# C-06_CPU_IO_PHY.net
KiCad netlist of a schematic drawn in Altium Designer
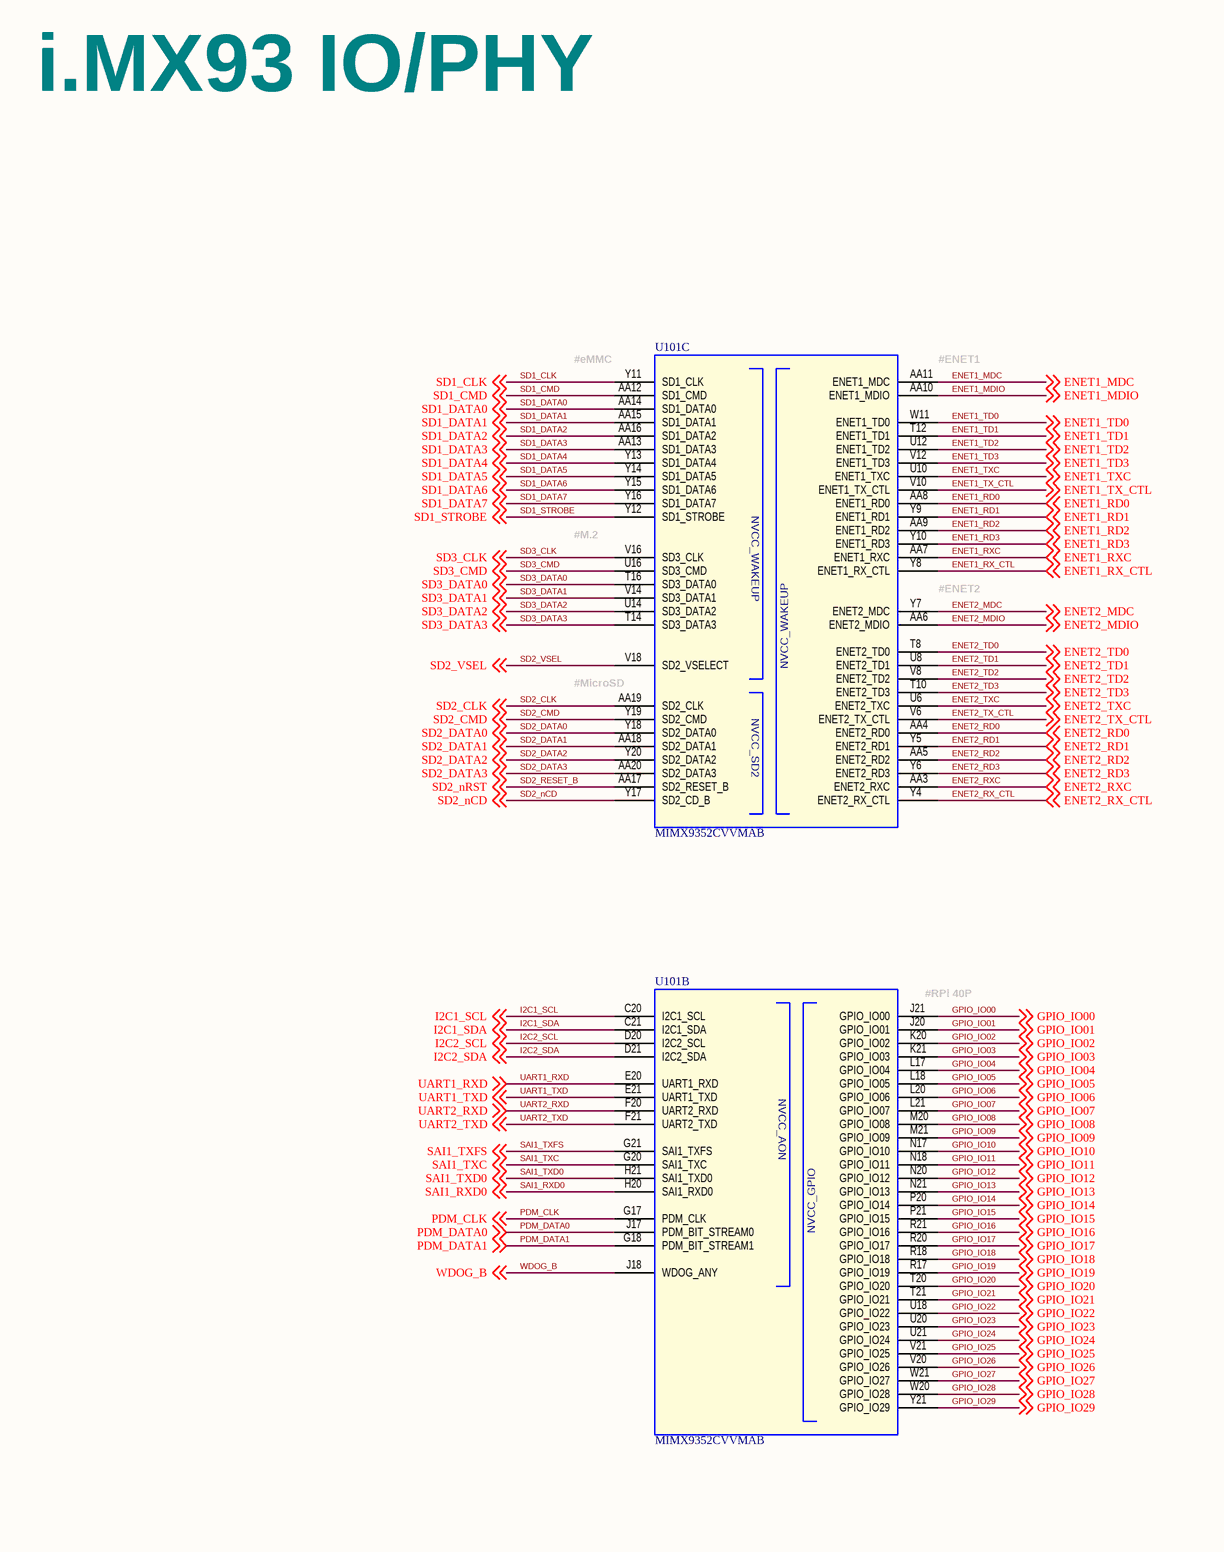
[diagram p0: C-06 CPU IO_PHY.SchDoc, left]
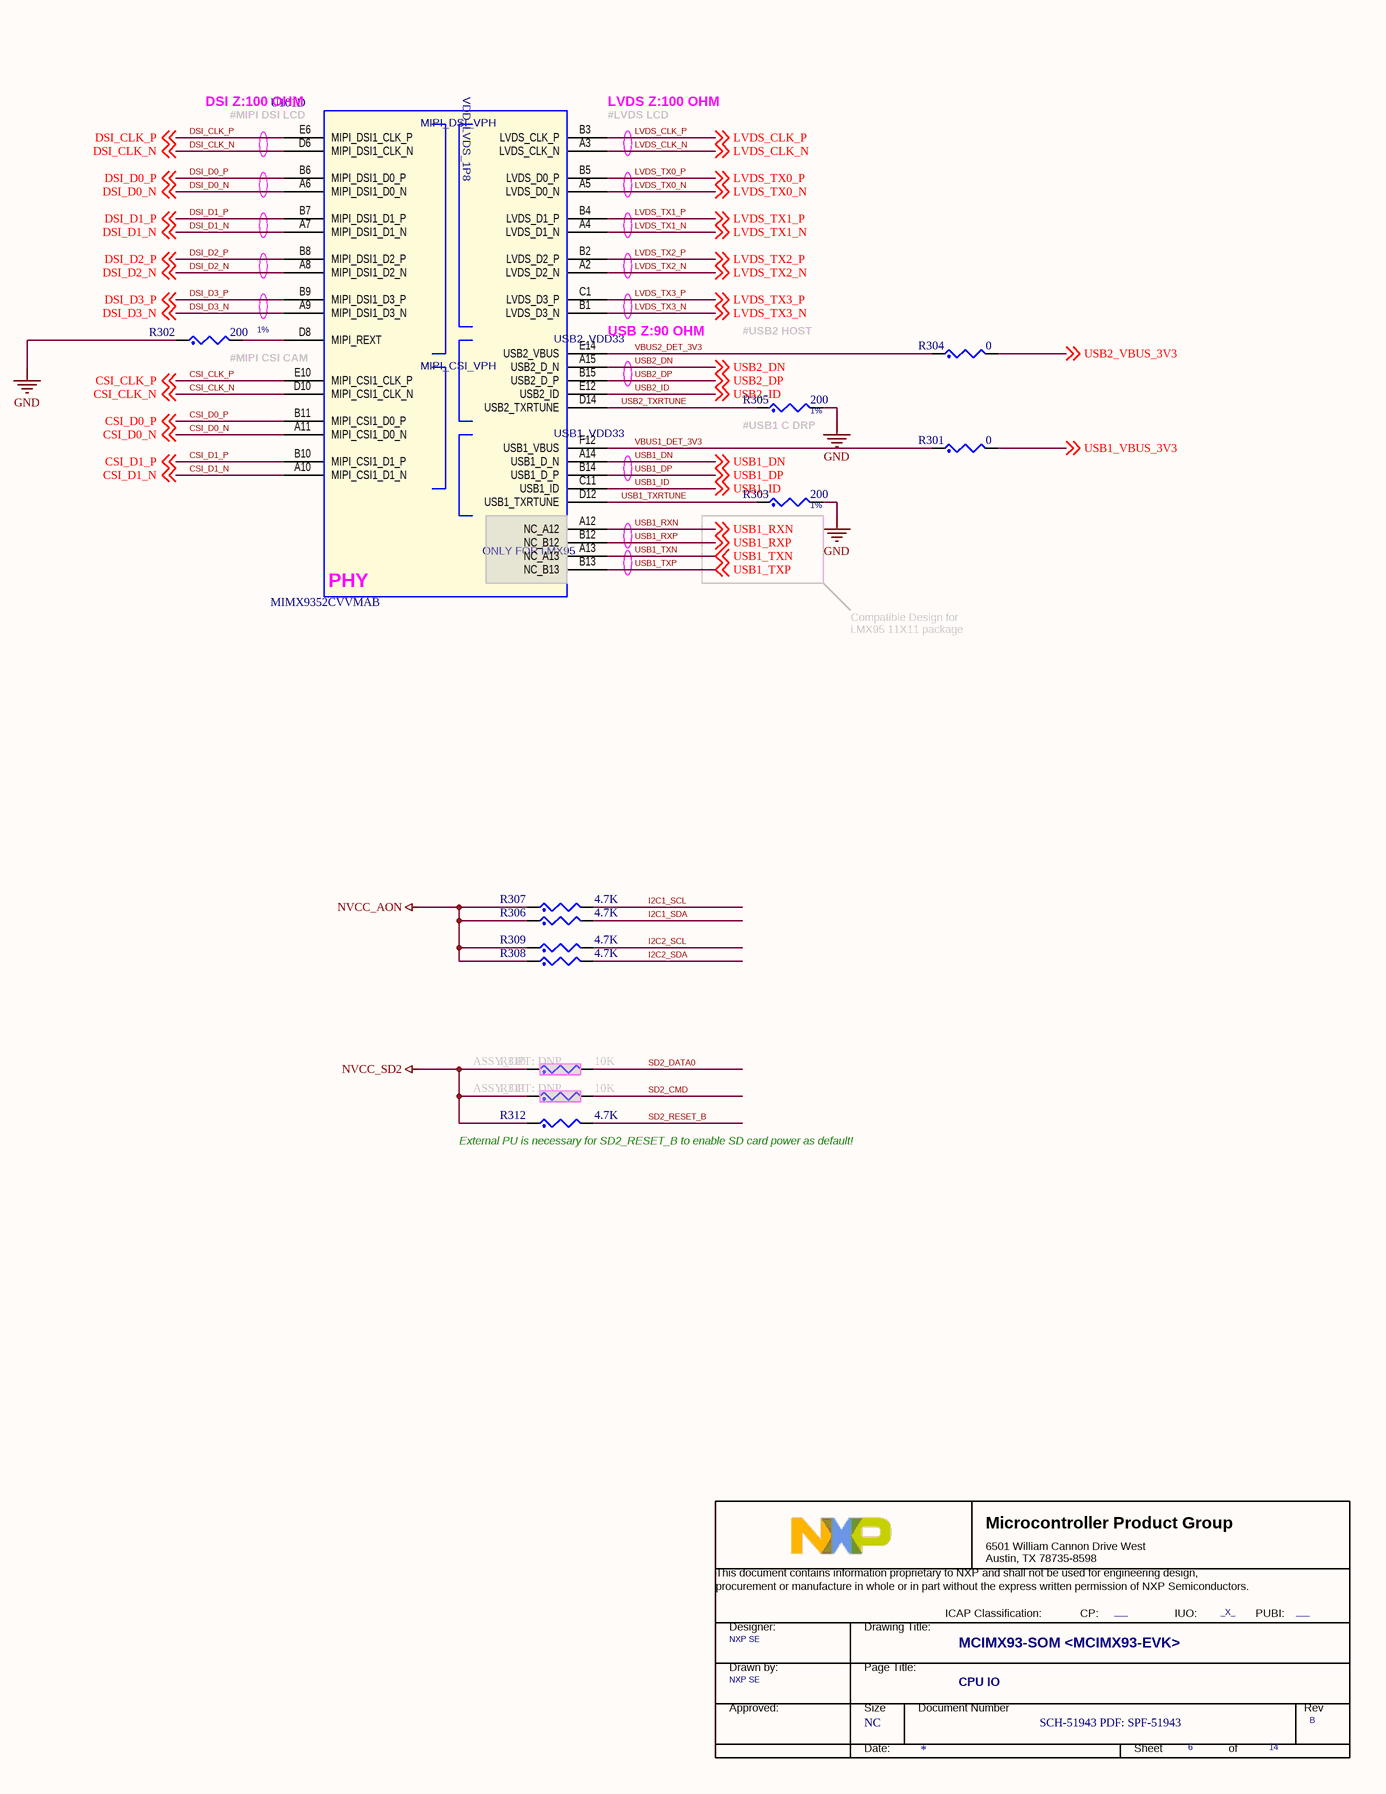
[diagram p1: C-06 CPU IO_PHY.SchDoc, right]

(export (version "E")
  (design (tool "Eeschema 10.0.6"))
  (components
    (comp (ref "R301")
      (value "0")
      (footprint "0201_CC")
      (description "RES MF ZERO OHM 1/20W -- 0201")
      (libsource (lib "*") (part "RES"))
    )
    (comp (ref "R302")
      (value "200")
      (footprint "0201_CC")
      (description "RES MF 200 OHM 1/20W 1% 0201")
      (fields (field (name "VOLTAGE") "25V") (field (name "TOLERANCE") "1%"))
      (libsource (lib "*") (part "RES"))
    )
    (comp (ref "R303")
      (value "200")
      (footprint "0201_CC")
      (description "RES MF 200 OHM 1/20W 1% 0201")
      (fields (field (name "TOLERANCE") "1%") (field (name "VOLTAGE") "25V"))
      (libsource (lib "*") (part "RES"))
    )
    (comp (ref "R304")
      (value "0")
      (footprint "0201_CC")
      (description "RES MF ZERO OHM 1/20W -- 0201")
      (libsource (lib "*") (part "RES"))
    )
    (comp (ref "R305")
      (value "200")
      (footprint "0201_CC")
      (description "RES MF 200 OHM 1/20W 1% 0201")
      (fields (field (name "TOLERANCE") "1%") (field (name "VOLTAGE") "25V"))
      (libsource (lib "*") (part "RES"))
    )
    (comp (ref "R306")
      (value "4.7K")
      (footprint "0402_CC")
      (description "RES MF 4.7K 1/10W 5% AEC-Q200 0402")
      (fields (field (name "VOLTAGE") "50V") (field (name "TOLERANCE") "5%"))
      (libsource (lib "*") (part "RES"))
    )
    (comp (ref "R307")
      (value "4.7K")
      (footprint "0402_CC")
      (description "RES MF 4.7K 1/10W 5% AEC-Q200 0402")
      (fields (field (name "TOLERANCE") "5%") (field (name "VOLTAGE") "50V"))
      (libsource (lib "*") (part "RES"))
    )
    (comp (ref "R308")
      (value "4.7K")
      (footprint "0402_CC")
      (description "RES MF 4.7K 1/10W 5% AEC-Q200 0402")
      (fields (field (name "TOLERANCE") "5%") (field (name "VOLTAGE") "50V"))
      (libsource (lib "*") (part "RES"))
    )
    (comp (ref "R309")
      (value "4.7K")
      (footprint "0402_CC")
      (description "RES MF 4.7K 1/10W 5% AEC-Q200 0402")
      (fields (field (name "TOLERANCE") "5%") (field (name "VOLTAGE") "50V"))
      (libsource (lib "*") (part "RES"))
    )
    (comp (ref "R310")
      (value "10K")
      (footprint "0402_CC")
      (description "RES MF 10K 1/16W 5% 0402")
      (fields (field (name "ASSY_OPT") "DNP") (field (name "TOLERANCE") "5%"))
      (libsource (lib "*") (part "RES"))
    )
    (comp (ref "R311")
      (value "10K")
      (footprint "0402_CC")
      (description "RES MF 10K 1/16W 5% 0402")
      (fields (field (name "ASSY_OPT") "DNP") (field (name "TOLERANCE") "5%"))
      (libsource (lib "*") (part "RES"))
    )
    (comp (ref "R312")
      (value "4.7K")
      (footprint "0402_CC")
      (description "RES MF 4.7K 1/10W 5% AEC-Q200 0402")
      (fields (field (name "TOLERANCE") "5%") (field (name "VOLTAGE") "50V"))
      (libsource (lib "*") (part "RES"))
    )
    (comp (ref "U101")
      (value "MIMX9352CVVMAB")
      (footprint "SKT_BGA306_0P5_SQ16P23_ELAST")
      (description "SUBASSEMBLY SKT 306 BGA ELASTOMER SMT 0.5MM 395H AU + IC CPU 1.7GHz -- FCBGA306")
      (libsource (lib "*") (part "MIMX9352DVNxLAA"))
    )
  )
  (nets
    (net (code "1") (name "/USB1_TXRTUNE") (class "Default")
      (node (ref "R303") (pin "1") (pinfunction "1_1") (pintype "passive"))
      (node (ref "U101") (pin "D12") (pinfunction "USB1_TXRTUNE_D12") (pintype "passive"))
    )
    (net (code "2") (name "/USB2_TXRTUNE") (class "Default")
      (node (ref "R305") (pin "1") (pinfunction "1_1") (pintype "passive"))
      (node (ref "U101") (pin "D14") (pinfunction "USB2_TXRTUNE_D14") (pintype "passive"))
    )
    (net (code "3") (name "/VBUS1_DET_3V3") (class "Default")
      (node (ref "R301") (pin "1") (pinfunction "1_1") (pintype "passive"))
      (node (ref "U101") (pin "F12") (pinfunction "USB1_VBUS_F12") (pintype "passive"))
    )
    (net (code "4") (name "/VBUS2_DET_3V3") (class "Default")
      (node (ref "R304") (pin "1") (pinfunction "1_1") (pintype "passive"))
      (node (ref "U101") (pin "E14") (pinfunction "USB2_VBUS_E14") (pintype "passive"))
    )
    (net (code "5") (name "CSI_CLK_N") (class "Default")
      (node (ref "U101") (pin "D10") (pinfunction "MIPI_CSI1_CLK_N_D10") (pintype "passive"))
    )
    (net (code "6") (name "CSI_CLK_P") (class "Default")
      (node (ref "U101") (pin "E10") (pinfunction "MIPI_CSI1_CLK_P_E10") (pintype "passive"))
    )
    (net (code "7") (name "CSI_D0_N") (class "Default")
      (node (ref "U101") (pin "A11") (pinfunction "MIPI_CSI1_D0_N_A11") (pintype "passive"))
    )
    (net (code "8") (name "CSI_D0_P") (class "Default")
      (node (ref "U101") (pin "B11") (pinfunction "MIPI_CSI1_D0_P_B11") (pintype "passive"))
    )
    (net (code "9") (name "CSI_D1_N") (class "Default")
      (node (ref "U101") (pin "A10") (pinfunction "MIPI_CSI1_D1_N_A10") (pintype "passive"))
    )
    (net (code "10") (name "CSI_D1_P") (class "Default")
      (node (ref "U101") (pin "B10") (pinfunction "MIPI_CSI1_D1_P_B10") (pintype "passive"))
    )
    (net (code "11") (name "DSI_CLK_N") (class "Default")
      (node (ref "U101") (pin "D6") (pinfunction "MIPI_DSI1_CLK_N_D6") (pintype "passive"))
    )
    (net (code "12") (name "DSI_CLK_P") (class "Default")
      (node (ref "U101") (pin "E6") (pinfunction "MIPI_DSI1_CLK_P_E6") (pintype "passive"))
    )
    (net (code "13") (name "DSI_D0_N") (class "Default")
      (node (ref "U101") (pin "A6") (pinfunction "MIPI_DSI1_D0_N_A6") (pintype "passive"))
    )
    (net (code "14") (name "DSI_D0_P") (class "Default")
      (node (ref "U101") (pin "B6") (pinfunction "MIPI_DSI1_D0_P_B6") (pintype "passive"))
    )
    (net (code "15") (name "DSI_D1_N") (class "Default")
      (node (ref "U101") (pin "A7") (pinfunction "MIPI_DSI1_D1_N_A7") (pintype "passive"))
    )
    (net (code "16") (name "DSI_D1_P") (class "Default")
      (node (ref "U101") (pin "B7") (pinfunction "MIPI_DSI1_D1_P_B7") (pintype "passive"))
    )
    (net (code "17") (name "DSI_D2_N") (class "Default")
      (node (ref "U101") (pin "A8") (pinfunction "MIPI_DSI1_D2_N_A8") (pintype "passive"))
    )
    (net (code "18") (name "DSI_D2_P") (class "Default")
      (node (ref "U101") (pin "B8") (pinfunction "MIPI_DSI1_D2_P_B8") (pintype "passive"))
    )
    (net (code "19") (name "DSI_D3_N") (class "Default")
      (node (ref "U101") (pin "A9") (pinfunction "MIPI_DSI1_D3_N_A9") (pintype "passive"))
    )
    (net (code "20") (name "DSI_D3_P") (class "Default")
      (node (ref "U101") (pin "B9") (pinfunction "MIPI_DSI1_D3_P_B9") (pintype "passive"))
    )
    (net (code "21") (name "ENET1_MDC") (class "Default")
      (node (ref "U101") (pin "AA11") (pinfunction "ENET1_MDC_AA11") (pintype "passive"))
    )
    (net (code "22") (name "ENET1_MDIO") (class "Default")
      (node (ref "U101") (pin "AA10") (pinfunction "ENET1_MDIO_AA10") (pintype "passive"))
    )
    (net (code "23") (name "ENET1_RD0") (class "Default")
      (node (ref "U101") (pin "AA8") (pinfunction "ENET1_RD0_AA8") (pintype "passive"))
    )
    (net (code "24") (name "ENET1_RD1") (class "Default")
      (node (ref "U101") (pin "Y9") (pinfunction "ENET1_RD1_Y9") (pintype "passive"))
    )
    (net (code "25") (name "ENET1_RD2") (class "Default")
      (node (ref "U101") (pin "AA9") (pinfunction "ENET1_RD2_AA9") (pintype "passive"))
    )
    (net (code "26") (name "ENET1_RD3") (class "Default")
      (node (ref "U101") (pin "Y10") (pinfunction "ENET1_RD3_Y10") (pintype "passive"))
    )
    (net (code "27") (name "ENET1_RXC") (class "Default")
      (node (ref "U101") (pin "AA7") (pinfunction "ENET1_RXC_AA7") (pintype "passive"))
    )
    (net (code "28") (name "ENET1_RX_CTL") (class "Default")
      (node (ref "U101") (pin "Y8") (pinfunction "ENET1_RX_CTL_Y8") (pintype "passive"))
    )
    (net (code "29") (name "ENET1_TD0") (class "Default")
      (node (ref "U101") (pin "W11") (pinfunction "ENET1_TD0_W11") (pintype "passive"))
    )
    (net (code "30") (name "ENET1_TD1") (class "Default")
      (node (ref "U101") (pin "T12") (pinfunction "ENET1_TD1_T12") (pintype "passive"))
    )
    (net (code "31") (name "ENET1_TD2") (class "Default")
      (node (ref "U101") (pin "U12") (pinfunction "ENET1_TD2_U12") (pintype "passive"))
    )
    (net (code "32") (name "ENET1_TD3") (class "Default")
      (node (ref "U101") (pin "V12") (pinfunction "ENET1_TD3_V12") (pintype "passive"))
    )
    (net (code "33") (name "ENET1_TXC") (class "Default")
      (node (ref "U101") (pin "U10") (pinfunction "ENET1_TXC_U10") (pintype "passive"))
    )
    (net (code "34") (name "ENET1_TX_CTL") (class "Default")
      (node (ref "U101") (pin "V10") (pinfunction "ENET1_TX_CTL_V10") (pintype "passive"))
    )
    (net (code "35") (name "ENET2_MDC") (class "Default")
      (node (ref "U101") (pin "Y7") (pinfunction "ENET2_MDC_Y7") (pintype "passive"))
    )
    (net (code "36") (name "ENET2_MDIO") (class "Default")
      (node (ref "U101") (pin "AA6") (pinfunction "ENET2_MDIO_AA6") (pintype "passive"))
    )
    (net (code "37") (name "ENET2_RD0") (class "Default")
      (node (ref "U101") (pin "AA4") (pinfunction "ENET2_RD0_AA4") (pintype "passive"))
    )
    (net (code "38") (name "ENET2_RD1") (class "Default")
      (node (ref "U101") (pin "Y5") (pinfunction "ENET2_RD1_Y5") (pintype "passive"))
    )
    (net (code "39") (name "ENET2_RD2") (class "Default")
      (node (ref "U101") (pin "AA5") (pinfunction "ENET2_RD2_AA5") (pintype "passive"))
    )
    (net (code "40") (name "ENET2_RD3") (class "Default")
      (node (ref "U101") (pin "Y6") (pinfunction "ENET2_RD3_Y6") (pintype "passive"))
    )
    (net (code "41") (name "ENET2_RXC") (class "Default")
      (node (ref "U101") (pin "AA3") (pinfunction "ENET2_RXC_AA3") (pintype "passive"))
    )
    (net (code "42") (name "ENET2_RX_CTL") (class "Default")
      (node (ref "U101") (pin "Y4") (pinfunction "ENET2_RX_CTL_Y4") (pintype "passive"))
    )
    (net (code "43") (name "ENET2_TD0") (class "Default")
      (node (ref "U101") (pin "T8") (pinfunction "ENET2_TD0_T8") (pintype "passive"))
    )
    (net (code "44") (name "ENET2_TD1") (class "Default")
      (node (ref "U101") (pin "U8") (pinfunction "ENET2_TD1_U8") (pintype "passive"))
    )
    (net (code "45") (name "ENET2_TD2") (class "Default")
      (node (ref "U101") (pin "V8") (pinfunction "ENET2_TD2_V8") (pintype "passive"))
    )
    (net (code "46") (name "ENET2_TD3") (class "Default")
      (node (ref "U101") (pin "T10") (pinfunction "ENET2_TD3_T10") (pintype "passive"))
    )
    (net (code "47") (name "ENET2_TXC") (class "Default")
      (node (ref "U101") (pin "U6") (pinfunction "ENET2_TXC_U6") (pintype "passive"))
    )
    (net (code "48") (name "ENET2_TX_CTL") (class "Default")
      (node (ref "U101") (pin "V6") (pinfunction "ENET2_TX_CTL_V6") (pintype "passive"))
    )
    (net (code "49") (name "GND") (class "Default")
      (node (ref "R302") (pin "1") (pinfunction "1_1") (pintype "passive"))
      (node (ref "R303") (pin "2") (pinfunction "2_2") (pintype "passive"))
      (node (ref "R305") (pin "2") (pinfunction "2_2") (pintype "passive"))
    )
    (net (code "50") (name "GPIO_IO00") (class "Default")
      (node (ref "U101") (pin "J21") (pinfunction "GPIO_IO00_J21") (pintype "passive"))
    )
    (net (code "51") (name "GPIO_IO01") (class "Default")
      (node (ref "U101") (pin "J20") (pinfunction "GPIO_IO01_J20") (pintype "passive"))
    )
    (net (code "52") (name "GPIO_IO02") (class "Default")
      (node (ref "U101") (pin "K20") (pinfunction "GPIO_IO02_K20") (pintype "passive"))
    )
    (net (code "53") (name "GPIO_IO03") (class "Default")
      (node (ref "U101") (pin "K21") (pinfunction "GPIO_IO03_K21") (pintype "passive"))
    )
    (net (code "54") (name "GPIO_IO04") (class "Default")
      (node (ref "U101") (pin "L17") (pinfunction "GPIO_IO04_L17") (pintype "passive"))
    )
    (net (code "55") (name "GPIO_IO05") (class "Default")
      (node (ref "U101") (pin "L18") (pinfunction "GPIO_IO05_L18") (pintype "passive"))
    )
    (net (code "56") (name "GPIO_IO06") (class "Default")
      (node (ref "U101") (pin "L20") (pinfunction "GPIO_IO06_L20") (pintype "passive"))
    )
    (net (code "57") (name "GPIO_IO07") (class "Default")
      (node (ref "U101") (pin "L21") (pinfunction "GPIO_IO07_L21") (pintype "passive"))
    )
    (net (code "58") (name "GPIO_IO08") (class "Default")
      (node (ref "U101") (pin "M20") (pinfunction "GPIO_IO08_M20") (pintype "passive"))
    )
    (net (code "59") (name "GPIO_IO09") (class "Default")
      (node (ref "U101") (pin "M21") (pinfunction "GPIO_IO09_M21") (pintype "passive"))
    )
    (net (code "60") (name "GPIO_IO10") (class "Default")
      (node (ref "U101") (pin "N17") (pinfunction "GPIO_IO10_N17") (pintype "passive"))
    )
    (net (code "61") (name "GPIO_IO11") (class "Default")
      (node (ref "U101") (pin "N18") (pinfunction "GPIO_IO11_N18") (pintype "passive"))
    )
    (net (code "62") (name "GPIO_IO12") (class "Default")
      (node (ref "U101") (pin "N20") (pinfunction "GPIO_IO12_N20") (pintype "passive"))
    )
    (net (code "63") (name "GPIO_IO13") (class "Default")
      (node (ref "U101") (pin "N21") (pinfunction "GPIO_IO13_N21") (pintype "passive"))
    )
    (net (code "64") (name "GPIO_IO14") (class "Default")
      (node (ref "U101") (pin "P20") (pinfunction "GPIO_IO14_P20") (pintype "passive"))
    )
    (net (code "65") (name "GPIO_IO15") (class "Default")
      (node (ref "U101") (pin "P21") (pinfunction "GPIO_IO15_P21") (pintype "passive"))
    )
    (net (code "66") (name "GPIO_IO16") (class "Default")
      (node (ref "U101") (pin "R21") (pinfunction "GPIO_IO16_R21") (pintype "passive"))
    )
    (net (code "67") (name "GPIO_IO17") (class "Default")
      (node (ref "U101") (pin "R20") (pinfunction "GPIO_IO17_R20") (pintype "passive"))
    )
    (net (code "68") (name "GPIO_IO18") (class "Default")
      (node (ref "U101") (pin "R18") (pinfunction "GPIO_IO18_R18") (pintype "passive"))
    )
    (net (code "69") (name "GPIO_IO19") (class "Default")
      (node (ref "U101") (pin "R17") (pinfunction "GPIO_IO19_R17") (pintype "passive"))
    )
    (net (code "70") (name "GPIO_IO20") (class "Default")
      (node (ref "U101") (pin "T20") (pinfunction "GPIO_IO20_T20") (pintype "passive"))
    )
    (net (code "71") (name "GPIO_IO21") (class "Default")
      (node (ref "U101") (pin "T21") (pinfunction "GPIO_IO21_T21") (pintype "passive"))
    )
    (net (code "72") (name "GPIO_IO22") (class "Default")
      (node (ref "U101") (pin "U18") (pinfunction "GPIO_IO22_U18") (pintype "passive"))
    )
    (net (code "73") (name "GPIO_IO23") (class "Default")
      (node (ref "U101") (pin "U20") (pinfunction "GPIO_IO23_U20") (pintype "passive"))
    )
    (net (code "74") (name "GPIO_IO24") (class "Default")
      (node (ref "U101") (pin "U21") (pinfunction "GPIO_IO24_U21") (pintype "passive"))
    )
    (net (code "75") (name "GPIO_IO25") (class "Default")
      (node (ref "U101") (pin "V21") (pinfunction "GPIO_IO25_V21") (pintype "passive"))
    )
    (net (code "76") (name "GPIO_IO26") (class "Default")
      (node (ref "U101") (pin "V20") (pinfunction "GPIO_IO26_V20") (pintype "passive"))
    )
    (net (code "77") (name "GPIO_IO27") (class "Default")
      (node (ref "U101") (pin "W21") (pinfunction "GPIO_IO27_W21") (pintype "passive"))
    )
    (net (code "78") (name "GPIO_IO28") (class "Default")
      (node (ref "U101") (pin "W20") (pinfunction "GPIO_IO28_W20") (pintype "passive"))
    )
    (net (code "79") (name "GPIO_IO29") (class "Default")
      (node (ref "U101") (pin "Y21") (pinfunction "GPIO_IO29_Y21") (pintype "passive"))
    )
    (net (code "80") (name "I2C1_SCL") (class "Default")
      (node (ref "R307") (pin "2") (pinfunction "2_2") (pintype "passive"))
      (node (ref "U101") (pin "C20") (pinfunction "I2C1_SCL_C20") (pintype "passive"))
    )
    (net (code "81") (name "I2C1_SDA") (class "Default")
      (node (ref "R306") (pin "2") (pinfunction "2_2") (pintype "passive"))
      (node (ref "U101") (pin "C21") (pinfunction "I2C1_SDA_C21") (pintype "passive"))
    )
    (net (code "82") (name "I2C2_SCL") (class "Default")
      (node (ref "R309") (pin "2") (pinfunction "2_2") (pintype "passive"))
      (node (ref "U101") (pin "D20") (pinfunction "I2C2_SCL_D20") (pintype "passive"))
    )
    (net (code "83") (name "I2C2_SDA") (class "Default")
      (node (ref "R308") (pin "2") (pinfunction "2_2") (pintype "passive"))
      (node (ref "U101") (pin "D21") (pinfunction "I2C2_SDA_D21") (pintype "passive"))
    )
    (net (code "84") (name "LVDS_CLK_N") (class "Default")
      (node (ref "U101") (pin "A3") (pinfunction "LVDS_CLK_N_A3") (pintype "passive"))
    )
    (net (code "85") (name "LVDS_CLK_P") (class "Default")
      (node (ref "U101") (pin "B3") (pinfunction "LVDS_CLK_P_B3") (pintype "passive"))
    )
    (net (code "86") (name "LVDS_TX0_N") (class "Default")
      (node (ref "U101") (pin "A5") (pinfunction "LVDS_D0_N_A5") (pintype "passive"))
    )
    (net (code "87") (name "LVDS_TX0_P") (class "Default")
      (node (ref "U101") (pin "B5") (pinfunction "LVDS_D0_P_B5") (pintype "passive"))
    )
    (net (code "88") (name "LVDS_TX1_N") (class "Default")
      (node (ref "U101") (pin "A4") (pinfunction "LVDS_D1_N_A4") (pintype "passive"))
    )
    (net (code "89") (name "LVDS_TX1_P") (class "Default")
      (node (ref "U101") (pin "B4") (pinfunction "LVDS_D1_P_B4") (pintype "passive"))
    )
    (net (code "90") (name "LVDS_TX2_N") (class "Default")
      (node (ref "U101") (pin "A2") (pinfunction "LVDS_D2_N_A2") (pintype "passive"))
    )
    (net (code "91") (name "LVDS_TX2_P") (class "Default")
      (node (ref "U101") (pin "B2") (pinfunction "LVDS_D2_P_B2") (pintype "passive"))
    )
    (net (code "92") (name "LVDS_TX3_N") (class "Default")
      (node (ref "U101") (pin "B1") (pinfunction "LVDS_D3_N_B1") (pintype "passive"))
    )
    (net (code "93") (name "LVDS_TX3_P") (class "Default")
      (node (ref "U101") (pin "C1") (pinfunction "LVDS_D3_P_C1") (pintype "passive"))
    )
    (net (code "94") (name "NVCC_AON") (class "Default")
      (node (ref "R306") (pin "1") (pinfunction "1_1") (pintype "passive"))
      (node (ref "R307") (pin "1") (pinfunction "1_1") (pintype "passive"))
      (node (ref "R308") (pin "1") (pinfunction "1_1") (pintype "passive"))
      (node (ref "R309") (pin "1") (pinfunction "1_1") (pintype "passive"))
    )
    (net (code "95") (name "NVCC_SD2") (class "Default")
      (node (ref "R310") (pin "1") (pinfunction "1_1") (pintype "passive"))
      (node (ref "R311") (pin "1") (pinfunction "1_1") (pintype "passive"))
      (node (ref "R312") (pin "1") (pinfunction "1_1") (pintype "passive"))
    )
    (net (code "96") (name "Net-(U101D-MIPI_REXT)") (class "Default")
      (node (ref "R302") (pin "2") (pinfunction "2_2") (pintype "passive"))
      (node (ref "U101") (pin "D8") (pinfunction "MIPI_REXT_D8") (pintype "passive"))
    )
    (net (code "97") (name "PDM_CLK") (class "Default")
      (node (ref "U101") (pin "G17") (pinfunction "PDM_CLK_G17") (pintype "passive"))
    )
    (net (code "98") (name "PDM_DATA0") (class "Default")
      (node (ref "U101") (pin "J17") (pinfunction "PDM_BIT_STREAM0_J17") (pintype "passive"))
    )
    (net (code "99") (name "PDM_DATA1") (class "Default")
      (node (ref "U101") (pin "G18") (pinfunction "PDM_BIT_STREAM1_G18") (pintype "passive"))
    )
    (net (code "100") (name "SAI1_RXD0") (class "Default")
      (node (ref "U101") (pin "H20") (pinfunction "SAI1_RXD0_H20") (pintype "passive"))
    )
    (net (code "101") (name "SAI1_TXC") (class "Default")
      (node (ref "U101") (pin "G20") (pinfunction "SAI1_TXC_G20") (pintype "passive"))
    )
    (net (code "102") (name "SAI1_TXD0") (class "Default")
      (node (ref "U101") (pin "H21") (pinfunction "SAI1_TXD0_H21") (pintype "passive"))
    )
    (net (code "103") (name "SAI1_TXFS") (class "Default")
      (node (ref "U101") (pin "G21") (pinfunction "SAI1_TXFS_G21") (pintype "passive"))
    )
    (net (code "104") (name "SD1_CLK") (class "Default")
      (node (ref "U101") (pin "Y11") (pinfunction "SD1_CLK_Y11") (pintype "passive"))
    )
    (net (code "105") (name "SD1_CMD") (class "Default")
      (node (ref "U101") (pin "AA12") (pinfunction "SD1_CMD_AA12") (pintype "passive"))
    )
    (net (code "106") (name "SD1_DATA0") (class "Default")
      (node (ref "U101") (pin "AA14") (pinfunction "SD1_DATA0_AA14") (pintype "passive"))
    )
    (net (code "107") (name "SD1_DATA1") (class "Default")
      (node (ref "U101") (pin "AA15") (pinfunction "SD1_DATA1_AA15") (pintype "passive"))
    )
    (net (code "108") (name "SD1_DATA2") (class "Default")
      (node (ref "U101") (pin "AA16") (pinfunction "SD1_DATA2_AA16") (pintype "passive"))
    )
    (net (code "109") (name "SD1_DATA3") (class "Default")
      (node (ref "U101") (pin "AA13") (pinfunction "SD1_DATA3_AA13") (pintype "passive"))
    )
    (net (code "110") (name "SD1_DATA4") (class "Default")
      (node (ref "U101") (pin "Y13") (pinfunction "SD1_DATA4_Y13") (pintype "passive"))
    )
    (net (code "111") (name "SD1_DATA5") (class "Default")
      (node (ref "U101") (pin "Y14") (pinfunction "SD1_DATA5_Y14") (pintype "passive"))
    )
    (net (code "112") (name "SD1_DATA6") (class "Default")
      (node (ref "U101") (pin "Y15") (pinfunction "SD1_DATA6_Y15") (pintype "passive"))
    )
    (net (code "113") (name "SD1_DATA7") (class "Default")
      (node (ref "U101") (pin "Y16") (pinfunction "SD1_DATA7_Y16") (pintype "passive"))
    )
    (net (code "114") (name "SD1_STROBE") (class "Default")
      (node (ref "U101") (pin "Y12") (pinfunction "SD1_STROBE_Y12") (pintype "passive"))
    )
    (net (code "115") (name "SD2_CLK") (class "Default")
      (node (ref "U101") (pin "AA19") (pinfunction "SD2_CLK_AA19") (pintype "passive"))
    )
    (net (code "116") (name "SD2_CMD") (class "Default")
      (node (ref "R311") (pin "2") (pinfunction "2_2") (pintype "passive"))
      (node (ref "U101") (pin "Y19") (pinfunction "SD2_CMD_Y19") (pintype "passive"))
    )
    (net (code "117") (name "SD2_DATA0") (class "Default")
      (node (ref "R310") (pin "2") (pinfunction "2_2") (pintype "passive"))
      (node (ref "U101") (pin "Y18") (pinfunction "SD2_DATA0_Y18") (pintype "passive"))
    )
    (net (code "118") (name "SD2_DATA1") (class "Default")
      (node (ref "U101") (pin "AA18") (pinfunction "SD2_DATA1_AA18") (pintype "passive"))
    )
    (net (code "119") (name "SD2_DATA2") (class "Default")
      (node (ref "U101") (pin "Y20") (pinfunction "SD2_DATA2_Y20") (pintype "passive"))
    )
    (net (code "120") (name "SD2_DATA3") (class "Default")
      (node (ref "U101") (pin "AA20") (pinfunction "SD2_DATA3_AA20") (pintype "passive"))
    )
    (net (code "121") (name "SD2_VSEL") (class "Default")
      (node (ref "U101") (pin "V18") (pinfunction "SD2_VSELECT_V18") (pintype "passive"))
    )
    (net (code "122") (name "SD2_nCD") (class "Default")
      (node (ref "U101") (pin "Y17") (pinfunction "SD2_CD_B_Y17") (pintype "passive"))
    )
    (net (code "123") (name "SD2_nRST") (class "Default")
      (node (ref "R312") (pin "2") (pinfunction "2_2") (pintype "passive"))
      (node (ref "U101") (pin "AA17") (pinfunction "SD2_RESET_B_AA17") (pintype "passive"))
    )
    (net (code "124") (name "SD3_CLK") (class "Default")
      (node (ref "U101") (pin "V16") (pinfunction "SD3_CLK_V16") (pintype "passive"))
    )
    (net (code "125") (name "SD3_CMD") (class "Default")
      (node (ref "U101") (pin "U16") (pinfunction "SD3_CMD_U16") (pintype "passive"))
    )
    (net (code "126") (name "SD3_DATA0") (class "Default")
      (node (ref "U101") (pin "T16") (pinfunction "SD3_DATA0_T16") (pintype "passive"))
    )
    (net (code "127") (name "SD3_DATA1") (class "Default")
      (node (ref "U101") (pin "V14") (pinfunction "SD3_DATA1_V14") (pintype "passive"))
    )
    (net (code "128") (name "SD3_DATA2") (class "Default")
      (node (ref "U101") (pin "U14") (pinfunction "SD3_DATA2_U14") (pintype "passive"))
    )
    (net (code "129") (name "SD3_DATA3") (class "Default")
      (node (ref "U101") (pin "T14") (pinfunction "SD3_DATA3_T14") (pintype "passive"))
    )
    (net (code "130") (name "UART1_RXD") (class "Default")
      (node (ref "U101") (pin "E20") (pinfunction "UART1_RXD_E20") (pintype "passive"))
    )
    (net (code "131") (name "UART1_TXD") (class "Default")
      (node (ref "U101") (pin "E21") (pinfunction "UART1_TXD_E21") (pintype "passive"))
    )
    (net (code "132") (name "UART2_RXD") (class "Default")
      (node (ref "U101") (pin "F20") (pinfunction "UART2_RXD_F20") (pintype "passive"))
    )
    (net (code "133") (name "UART2_TXD") (class "Default")
      (node (ref "U101") (pin "F21") (pinfunction "UART2_TXD_F21") (pintype "passive"))
    )
    (net (code "134") (name "USB1_DN") (class "Default")
      (node (ref "U101") (pin "A14") (pinfunction "USB1_D_N_A14") (pintype "passive"))
    )
    (net (code "135") (name "USB1_DP") (class "Default")
      (node (ref "U101") (pin "B14") (pinfunction "USB1_D_P_B14") (pintype "passive"))
    )
    (net (code "136") (name "USB1_ID") (class "Default")
      (node (ref "U101") (pin "C11") (pinfunction "USB1_ID_C11") (pintype "passive"))
    )
    (net (code "137") (name "USB1_RXN") (class "Default")
      (node (ref "U101") (pin "A12") (pinfunction "NC_A12_A12") (pintype "passive"))
    )
    (net (code "138") (name "USB1_RXP") (class "Default")
      (node (ref "U101") (pin "B12") (pinfunction "NC_B12_B12") (pintype "passive"))
    )
    (net (code "139") (name "USB1_TXN") (class "Default")
      (node (ref "U101") (pin "A13") (pinfunction "NC_A13_A13") (pintype "passive"))
    )
    (net (code "140") (name "USB1_TXP") (class "Default")
      (node (ref "U101") (pin "B13") (pinfunction "NC_B13_B13") (pintype "passive"))
    )
    (net (code "141") (name "USB1_VBUS_3V3") (class "Default")
      (node (ref "R301") (pin "2") (pinfunction "2_2") (pintype "passive"))
    )
    (net (code "142") (name "USB2_DN") (class "Default")
      (node (ref "U101") (pin "A15") (pinfunction "USB2_D_N_A15") (pintype "passive"))
    )
    (net (code "143") (name "USB2_DP") (class "Default")
      (node (ref "U101") (pin "B15") (pinfunction "USB2_D_P_B15") (pintype "passive"))
    )
    (net (code "144") (name "USB2_ID") (class "Default")
      (node (ref "U101") (pin "E12") (pinfunction "USB2_ID_E12") (pintype "passive"))
    )
    (net (code "145") (name "USB2_VBUS_3V3") (class "Default")
      (node (ref "R304") (pin "2") (pinfunction "2_2") (pintype "passive"))
    )
    (net (code "146") (name "WDOG_B") (class "Default")
      (node (ref "U101") (pin "J18") (pinfunction "WDOG_ANY_J18") (pintype "passive"))
    )
  )
)
